# I2C_LCD_Backpack_v28.net
KiCad netlist of a schematic drawn in EAGLE
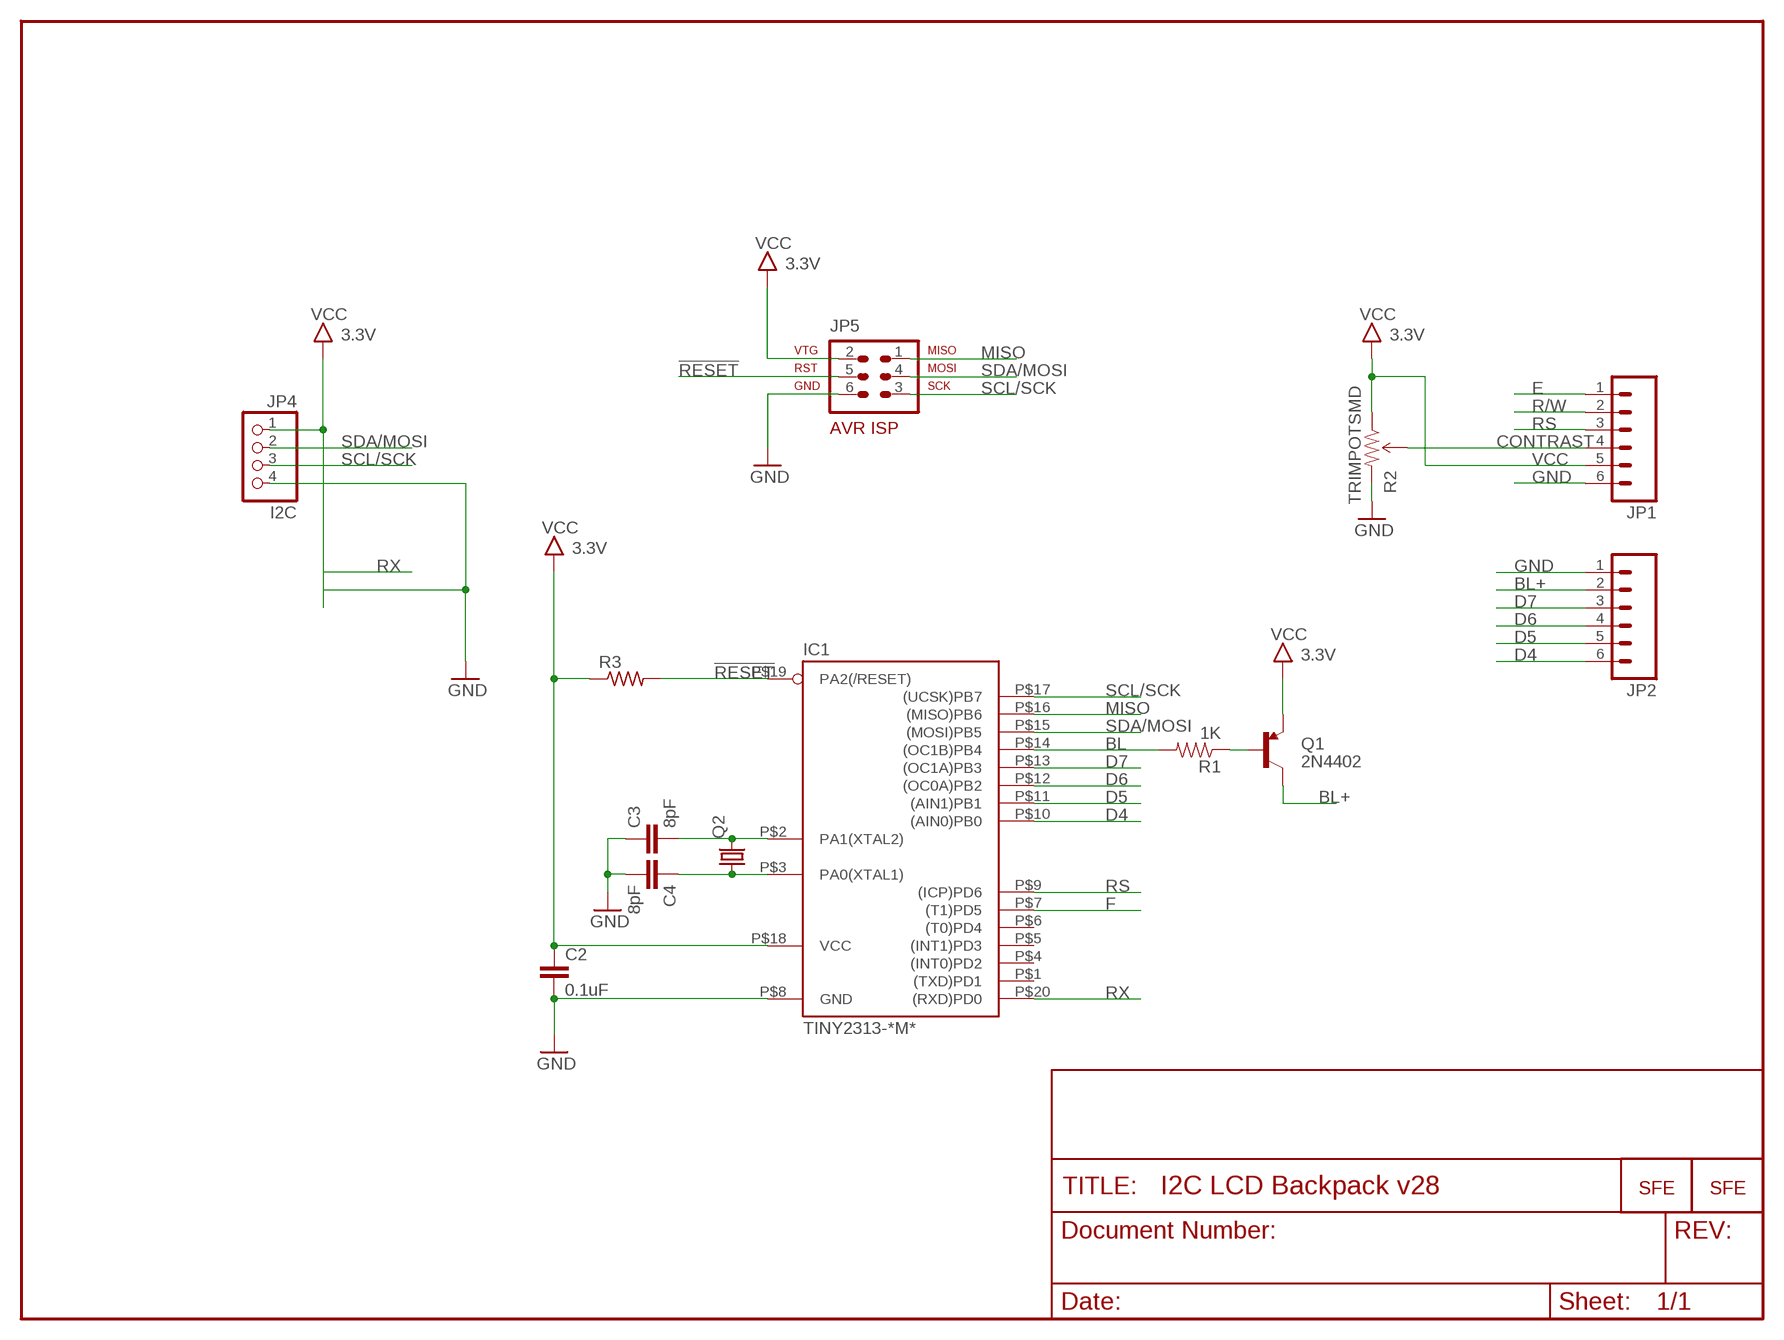
[diagram p0: schematic, sheet 1]

(export (version "E")
  (design (tool "Eeschema 10.0.6"))
  (components
    (comp (ref "C2")
      (value "0.1uF")
      (footprint "eagle-import:0603-CAP")
      (libsource (lib "eagle-import") (part "CAP0603-CAP"))
    )
    (comp (ref "C3")
      (value "8pF")
      (footprint "eagle-import:0603-CAP")
      (libsource (lib "eagle-import") (part "CAP0603-CAP"))
    )
    (comp (ref "C4")
      (value "8pF")
      (footprint "eagle-import:0603-CAP")
      (libsource (lib "eagle-import") (part "CAP0603-CAP"))
    )
    (comp (ref "IC1")
      (value "TINY2313-*M*")
      (footprint "eagle-import:MLF20")
      (libsource (lib "eagle-import") (part "TINY2313-M"))
    )
    (comp (ref "JP1")
      (value "M06LOCK")
      (footprint "eagle-import:1X06_LOCK")
      (libsource (lib "eagle-import") (part "M06LOCK"))
    )
    (comp (ref "JP2")
      (value "M06LOCK")
      (footprint "eagle-import:1X06_LOCK")
      (libsource (lib "eagle-import") (part "M06LOCK"))
    )
    (comp (ref "JP4")
      (value "I2C")
      (footprint "eagle-import:1X04-S")
      (libsource (lib "eagle-import") (part "PINHD-1X04_2.54-S"))
    )
    (comp (ref "JP5")
      (value "AVR-ISP-6")
      (footprint "eagle-import:AVR-ISP-6")
      (libsource (lib "eagle-import") (part "AVR-ISP-6"))
    )
    (comp (ref "Q1")
      (value "2N4402")
      (footprint "eagle-import:SOT23-3")
      (libsource (lib "eagle-import") (part "TRANSISTOR_PNPSMD"))
    )
    (comp (ref "Q2")
      (value "CRYSTALNDK5X3")
      (footprint "eagle-import:NDK_2PAD_5X3")
      (libsource (lib "eagle-import") (part "CRYSTALNDK5X3"))
    )
    (comp (ref "R1")
      (value "1K")
      (footprint "eagle-import:0402-RES")
      (libsource (lib "eagle-import") (part "RESISTOR0402-RES"))
    )
    (comp (ref "R2")
      (value "TRIMPOTSMD")
      (footprint "eagle-import:TRIMPOT-3MM")
      (libsource (lib "eagle-import") (part "TRIMPOTSMD"))
    )
    (comp (ref "R3")
      (value "R-US_R0603")
      (footprint "eagle-import:R0603")
      (libsource (lib "eagle-import") (part "R-US_R0603"))
    )
    (comp (ref "U$2")
      (value "LOGO-FLAME-LARGE")
      (footprint "eagle-import:LOGO-FLAME-LARGE")
      (libsource (lib "eagle-import") (part "LOGO-FLAME-LARGE"))
    )
    (comp (ref "U$5")
      (value "LOGO-SFENEW")
      (footprint "eagle-import:SFE-NEW-WEBLOGO")
      (libsource (lib "eagle-import") (part "LOGO-SFENEW"))
    )
  )
  (nets
    (net (code "1") (name "/BL") (class "Default")
      (node (ref "IC1") (pin "P$14") (pinfunction "(OC1B)PB4_P$14") (pintype "bidirectional"))
      (node (ref "R1") (pin "2") (pinfunction "2_2") (pintype "passive"))
    )
    (net (code "2") (name "/BL+") (class "Default")
      (node (ref "JP2") (pin "2") (pinfunction "2_2") (pintype "passive"))
      (node (ref "Q1") (pin "3") (pinfunction "C_3") (pintype "passive"))
    )
    (net (code "3") (name "/CONTRAST") (class "Default")
      (node (ref "JP1") (pin "4") (pinfunction "4_4") (pintype "passive"))
      (node (ref "R2") (pin "2") (pinfunction "WIPER_2") (pintype "passive"))
    )
    (net (code "4") (name "/D4") (class "Default")
      (node (ref "IC1") (pin "P$10") (pinfunction "(AIN0)PB0_P$10") (pintype "bidirectional"))
      (node (ref "JP2") (pin "6") (pinfunction "6_6") (pintype "passive"))
    )
    (net (code "5") (name "/D5") (class "Default")
      (node (ref "IC1") (pin "P$11") (pinfunction "(AIN1)PB1_P$11") (pintype "bidirectional"))
      (node (ref "JP2") (pin "5") (pinfunction "5_5") (pintype "passive"))
    )
    (net (code "6") (name "/D6") (class "Default")
      (node (ref "IC1") (pin "P$12") (pinfunction "(OC0A)PB2_P$12") (pintype "bidirectional"))
      (node (ref "JP2") (pin "4") (pinfunction "4_4") (pintype "passive"))
    )
    (net (code "7") (name "/D7") (class "Default")
      (node (ref "IC1") (pin "P$13") (pinfunction "(OC1A)PB3_P$13") (pintype "bidirectional"))
      (node (ref "JP2") (pin "3") (pinfunction "3_3") (pintype "passive"))
    )
    (net (code "8") (name "/E") (class "Default")
      (node (ref "JP1") (pin "1") (pinfunction "1_1") (pintype "passive"))
    )
    (net (code "9") (name "/F") (class "Default")
      (node (ref "IC1") (pin "P$7") (pinfunction "(T1)PD5_P$7") (pintype "bidirectional"))
    )
    (net (code "10") (name "/MISO") (class "Default")
      (node (ref "IC1") (pin "P$16") (pinfunction "(MISO)PB6_P$16") (pintype "bidirectional"))
      (node (ref "JP5") (pin "1") (pinfunction "1_1") (pintype "passive"))
    )
    (net (code "11") (name "/RS") (class "Default")
      (node (ref "IC1") (pin "P$9") (pinfunction "(ICP)PD6_P$9") (pintype "bidirectional"))
      (node (ref "JP1") (pin "3") (pinfunction "3_3") (pintype "passive"))
    )
    (net (code "12") (name "/RX") (class "Default")
      (node (ref "IC1") (pin "P$20") (pinfunction "(RXD)PD0_P$20") (pintype "bidirectional"))
    )
    (net (code "13") (name "/R{slash}W") (class "Default")
      (node (ref "JP1") (pin "2") (pinfunction "2_2") (pintype "passive"))
    )
    (net (code "14") (name "/SCL{slash}SCK") (class "Default")
      (node (ref "IC1") (pin "P$17") (pinfunction "(UCSK)PB7_P$17") (pintype "bidirectional"))
      (node (ref "JP4") (pin "3") (pinfunction "3_3") (pintype "passive"))
      (node (ref "JP5") (pin "3") (pinfunction "3_3") (pintype "passive"))
    )
    (net (code "15") (name "/SDA{slash}MOSI") (class "Default")
      (node (ref "IC1") (pin "P$15") (pinfunction "(MOSI)PB5_P$15") (pintype "bidirectional"))
      (node (ref "JP4") (pin "2") (pinfunction "2_2") (pintype "passive"))
      (node (ref "JP5") (pin "4") (pinfunction "4_4") (pintype "passive"))
    )
    (net (code "16") (name "/~{RESET}") (class "Default")
      (node (ref "IC1") (pin "P$19") (pinfunction "PA2(/RESET)_P$19") (pintype "input"))
      (node (ref "JP5") (pin "5") (pinfunction "5_5") (pintype "passive"))
      (node (ref "R3") (pin "2") (pinfunction "2_2") (pintype "passive"))
    )
    (net (code "17") (name "3.3V") (class "Default")
      (node (ref "C2") (pin "1") (pinfunction "1_1") (pintype "passive"))
      (node (ref "IC1") (pin "P$18") (pinfunction "VCC_P$18") (pintype "power_in"))
      (node (ref "JP1") (pin "5") (pinfunction "5_5") (pintype "passive"))
      (node (ref "JP4") (pin "1") (pinfunction "1_1") (pintype "passive"))
      (node (ref "JP5") (pin "2") (pinfunction "2_2") (pintype "passive"))
      (node (ref "Q1") (pin "2") (pinfunction "E_2") (pintype "passive"))
      (node (ref "R2") (pin "1") (pinfunction "CCW_1") (pintype "passive"))
      (node (ref "R3") (pin "1") (pinfunction "1_1") (pintype "passive"))
    )
    (net (code "18") (name "GND") (class "Default")
      (node (ref "C2") (pin "2") (pinfunction "2_2") (pintype "passive"))
      (node (ref "C3") (pin "1") (pinfunction "1_1") (pintype "passive"))
      (node (ref "C4") (pin "2") (pinfunction "2_2") (pintype "passive"))
      (node (ref "IC1") (pin "P$8") (pinfunction "GND_P$8") (pintype "power_in"))
      (node (ref "JP1") (pin "6") (pinfunction "6_6") (pintype "passive"))
      (node (ref "JP2") (pin "1") (pinfunction "1_1") (pintype "passive"))
      (node (ref "JP4") (pin "4") (pinfunction "4_4") (pintype "passive"))
      (node (ref "JP5") (pin "6") (pinfunction "6_6") (pintype "passive"))
      (node (ref "R2") (pin "3") (pinfunction "CW_3") (pintype "passive"))
    )
    (net (code "19") (name "Net-(IC1-PA0(XTAL1))") (class "Default")
      (node (ref "C4") (pin "1") (pinfunction "1_1") (pintype "passive"))
      (node (ref "IC1") (pin "P$3") (pinfunction "PA0(XTAL1)_P$3") (pintype "bidirectional"))
      (node (ref "Q2") (pin "P$1") (pinfunction "1_P$1") (pintype "passive"))
    )
    (net (code "20") (name "Net-(IC1-PA1(XTAL2))") (class "Default")
      (node (ref "C3") (pin "2") (pinfunction "2_2") (pintype "passive"))
      (node (ref "IC1") (pin "P$2") (pinfunction "PA1(XTAL2)_P$2") (pintype "bidirectional"))
      (node (ref "Q2") (pin "P$2") (pinfunction "2_P$2") (pintype "passive"))
    )
    (net (code "21") (name "Net-(Q1-B)") (class "Default")
      (node (ref "Q1") (pin "1") (pinfunction "B_1") (pintype "passive"))
      (node (ref "R1") (pin "1") (pinfunction "1_1") (pintype "passive"))
    )
    (net (code "22") (name "unconnected-(IC1-(INT0)PD2-PadP$4)") (class "Default")
      (node (ref "IC1") (pin "P$4") (pinfunction "(INT0)PD2_P$4") (pintype "bidirectional"))
    )
    (net (code "23") (name "unconnected-(IC1-(INT1)PD3-PadP$5)") (class "Default")
      (node (ref "IC1") (pin "P$5") (pinfunction "(INT1)PD3_P$5") (pintype "bidirectional"))
    )
    (net (code "24") (name "unconnected-(IC1-(T0)PD4-PadP$6)") (class "Default")
      (node (ref "IC1") (pin "P$6") (pinfunction "(T0)PD4_P$6") (pintype "bidirectional"))
    )
    (net (code "25") (name "unconnected-(IC1-(TXD)PD1-PadP$1)") (class "Default")
      (node (ref "IC1") (pin "P$1") (pinfunction "(TXD)PD1_P$1") (pintype "bidirectional"))
    )
  )
)
